# circuitdraft.net
KiCad netlist of a schematic drawn in EAGLE
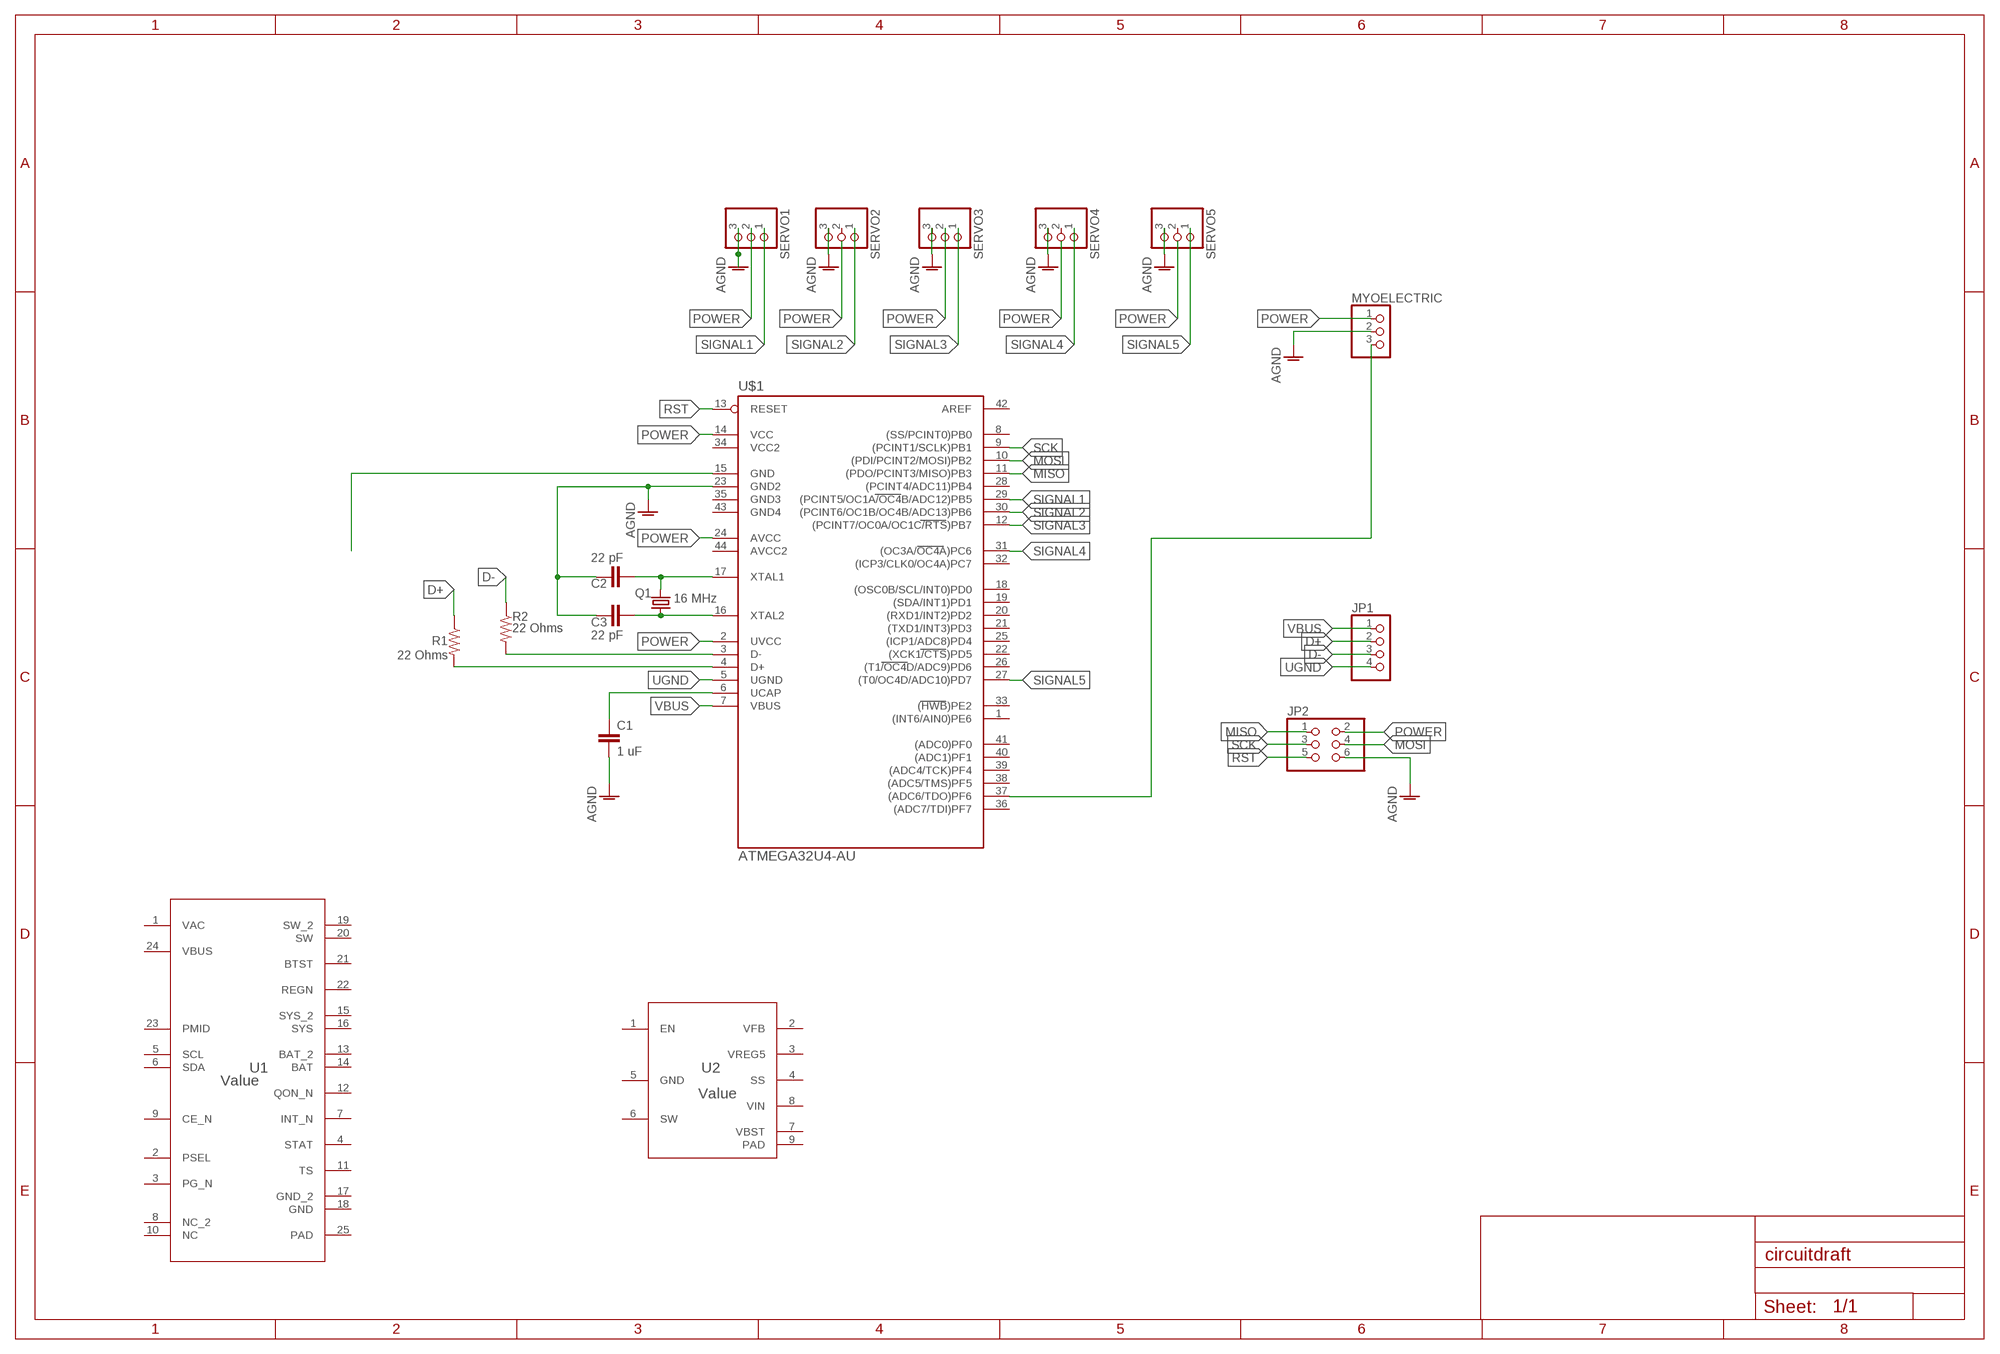
[diagram p0: schematic, sheet 1]

(export (version "E")
  (design (tool "Eeschema 10.0.6"))
  (components
    (comp (ref "C1")
      (value "1 uF")
      (footprint "eagle-import:C2.5-3")
      (libsource (lib "eagle-import") (part "C2,5-3"))
    )
    (comp (ref "C2")
      (value "22 pF")
      (footprint "eagle-import:C2.5-3")
      (libsource (lib "eagle-import") (part "C2,5-3"))
    )
    (comp (ref "C3")
      (value "22 pF")
      (footprint "eagle-import:C2.5-3")
      (libsource (lib "eagle-import") (part "C2,5-3"))
    )
    (comp (ref "JP1")
      (value "PINHD-1X4")
      (footprint "eagle-import:1X04")
      (libsource (lib "eagle-import") (part "PINHD-1X4"))
    )
    (comp (ref "JP2")
      (value "PINHD-2X3")
      (footprint "eagle-import:2X03")
      (libsource (lib "eagle-import") (part "PINHD-2X3"))
    )
    (comp (ref "MYOELECTRIC")
      (value "PINHD-1X3")
      (footprint "eagle-import:1X03")
      (libsource (lib "eagle-import") (part "PINHD-1X3"))
    )
    (comp (ref "Q1")
      (value "16 MHz")
      (footprint "eagle-import:HC49_S")
      (libsource (lib "eagle-import") (part "CRYSTALHC49S"))
    )
    (comp (ref "R1")
      (value "22 Ohms")
      (footprint "eagle-import:0204_7")
      (libsource (lib "eagle-import") (part "R-US_0204/7"))
    )
    (comp (ref "R2")
      (value "22 Ohms")
      (footprint "eagle-import:0204_7")
      (libsource (lib "eagle-import") (part "R-US_0204/7"))
    )
    (comp (ref "SERVO1")
      (value "PINHD-1X3")
      (footprint "eagle-import:1X03")
      (libsource (lib "eagle-import") (part "PINHD-1X3"))
    )
    (comp (ref "SERVO2")
      (value "PINHD-1X3")
      (footprint "eagle-import:1X03")
      (libsource (lib "eagle-import") (part "PINHD-1X3"))
    )
    (comp (ref "SERVO3")
      (value "PINHD-1X3")
      (footprint "eagle-import:1X03")
      (libsource (lib "eagle-import") (part "PINHD-1X3"))
    )
    (comp (ref "SERVO4")
      (value "PINHD-1X3")
      (footprint "eagle-import:1X03")
      (libsource (lib "eagle-import") (part "PINHD-1X3"))
    )
    (comp (ref "SERVO5")
      (value "PINHD-1X3")
      (footprint "eagle-import:1X03")
      (libsource (lib "eagle-import") (part "PINHD-1X3"))
    )
    (comp (ref "U$1")
      (value "ATMEGA32U4-AU")
      (footprint "eagle-import:TQFP44")
      (libsource (lib "eagle-import") (part "ATMEGA32U4-AU"))
    )
    (comp (ref "U1")
      (value "Value")
      (footprint "eagle-import:RTW0024H")
      (fields (field (name "MANUFACTURER") "Texas Instruments") (field (name "PARTNUMBER") "BQ25601RTWR"))
      (libsource (lib "eagle-import") (part "BQ25601RTWR"))
    )
    (comp (ref "U2")
      (value "Value")
      (footprint "eagle-import:DDA0008E_N")
      (fields
        (field (name "MANUFACTURER") "Texas Instruments")
        (field (name "PARTNUMBER") "UCC27211AQDDARQ1")
      )
      (libsource (lib "eagle-import") (part "UCC27211AQDDARQ1"))
    )
  )
  (nets
    (net (code "1") (name "/BAT") (class "Default")
      (node (ref "U1") (pin "14") (pinfunction "BAT_14") (pintype "power_in"))
    )
    (net (code "2") (name "/BAT_2") (class "Default")
      (node (ref "U1") (pin "13") (pinfunction "BAT_2_13") (pintype "power_in"))
    )
    (net (code "3") (name "/BTST") (class "Default")
      (node (ref "U1") (pin "21") (pinfunction "BTST_21") (pintype "power_in"))
    )
    (net (code "4") (name "/EN") (class "Default")
      (node (ref "U2") (pin "1") (pinfunction "EN_1") (pintype "power_in"))
    )
    (net (code "5") (name "/GND") (class "Default")
      (node (ref "U1") (pin "18") (pinfunction "GND_18") (pintype "power_in"))
    )
    (net (code "6") (name "/GND_2") (class "Default")
      (node (ref "U1") (pin "17") (pinfunction "GND_2_17") (pintype "power_in"))
    )
    (net (code "7") (name "/PAD") (class "Default")
      (node (ref "U1") (pin "25") (pinfunction "PAD_25") (pintype "power_in"))
    )
    (net (code "8") (name "/REGN") (class "Default")
      (node (ref "U1") (pin "22") (pinfunction "REGN_22") (pintype "power_in"))
    )
    (net (code "9") (name "/SS") (class "Default")
      (node (ref "U2") (pin "4") (pinfunction "SS_4") (pintype "power_in"))
    )
    (net (code "10") (name "/SW") (class "Default")
      (node (ref "U1") (pin "20") (pinfunction "SW_20") (pintype "power_in"))
    )
    (net (code "11") (name "/SW_2") (class "Default")
      (node (ref "U1") (pin "19") (pinfunction "SW_2_19") (pintype "power_in"))
    )
    (net (code "12") (name "/SYS") (class "Default")
      (node (ref "U1") (pin "16") (pinfunction "SYS_16") (pintype "power_in"))
    )
    (net (code "13") (name "/SYS_2") (class "Default")
      (node (ref "U1") (pin "15") (pinfunction "SYS_2_15") (pintype "power_in"))
    )
    (net (code "14") (name "/VAC") (class "Default")
      (node (ref "U1") (pin "1") (pinfunction "VAC_1") (pintype "power_in"))
    )
    (net (code "15") (name "/VBST") (class "Default")
      (node (ref "U2") (pin "7") (pinfunction "VBST_7") (pintype "power_in"))
    )
    (net (code "16") (name "/VFB") (class "Default")
      (node (ref "U2") (pin "2") (pinfunction "VFB_2") (pintype "power_in"))
    )
    (net (code "17") (name "AGND") (class "Default")
      (node (ref "C1") (pin "2") (pinfunction "2_2") (pintype "passive"))
      (node (ref "C2") (pin "1") (pinfunction "1_1") (pintype "passive"))
      (node (ref "C3") (pin "1") (pinfunction "1_1") (pintype "passive"))
      (node (ref "JP2") (pin "6") (pinfunction "6_6") (pintype "passive"))
      (node (ref "MYOELECTRIC") (pin "2") (pinfunction "2_2") (pintype "passive"))
      (node (ref "SERVO1") (pin "3") (pinfunction "3_3") (pintype "passive"))
      (node (ref "SERVO2") (pin "3") (pinfunction "3_3") (pintype "passive"))
      (node (ref "SERVO3") (pin "3") (pinfunction "3_3") (pintype "passive"))
      (node (ref "SERVO4") (pin "3") (pinfunction "3_3") (pintype "passive"))
      (node (ref "SERVO5") (pin "3") (pinfunction "3_3") (pintype "passive"))
      (node (ref "U$1") (pin "23") (pinfunction "GND2_23") (pintype "bidirectional"))
    )
    (net (code "18") (name "D+") (class "Default")
      (node (ref "JP1") (pin "2") (pinfunction "2_2") (pintype "passive"))
      (node (ref "R1") (pin "1") (pinfunction "1_1") (pintype "passive"))
    )
    (net (code "19") (name "D-") (class "Default")
      (node (ref "JP1") (pin "3") (pinfunction "3_3") (pintype "passive"))
      (node (ref "R2") (pin "1") (pinfunction "1_1") (pintype "passive"))
    )
    (net (code "20") (name "MISO") (class "Default")
      (node (ref "JP2") (pin "1") (pinfunction "1_1") (pintype "passive"))
      (node (ref "U$1") (pin "11") (pinfunction "(PDO/PCINT3/MISO)PB3_11") (pintype "bidirectional"))
    )
    (net (code "21") (name "MOSI") (class "Default")
      (node (ref "JP2") (pin "4") (pinfunction "4_4") (pintype "passive"))
      (node (ref "U$1") (pin "10") (pinfunction "(PDI/PCINT2/MOSI)PB2_10") (pintype "bidirectional"))
    )
    (net (code "22") (name "Net-(U$1-(ADC6{slash}TDO)PF6)") (class "Default")
      (node (ref "MYOELECTRIC") (pin "3") (pinfunction "3_3") (pintype "passive"))
      (node (ref "U$1") (pin "37") (pinfunction "(ADC6/TDO)PF6_37") (pintype "bidirectional"))
    )
    (net (code "23") (name "Net-(U$1-D+)") (class "Default")
      (node (ref "R1") (pin "2") (pinfunction "2_2") (pintype "passive"))
      (node (ref "U$1") (pin "4") (pinfunction "D+_4") (pintype "bidirectional"))
    )
    (net (code "24") (name "Net-(U$1-D-)") (class "Default")
      (node (ref "R2") (pin "2") (pinfunction "2_2") (pintype "passive"))
      (node (ref "U$1") (pin "3") (pinfunction "D-_3") (pintype "bidirectional"))
    )
    (net (code "25") (name "Net-(U$1-UCAP)") (class "Default")
      (node (ref "C1") (pin "1") (pinfunction "1_1") (pintype "passive"))
      (node (ref "U$1") (pin "6") (pinfunction "UCAP_6") (pintype "bidirectional"))
    )
    (net (code "26") (name "Net-(U$1-XTAL1)") (class "Default")
      (node (ref "C2") (pin "2") (pinfunction "2_2") (pintype "passive"))
      (node (ref "Q1") (pin "2") (pinfunction "2_2") (pintype "passive"))
      (node (ref "U$1") (pin "17") (pinfunction "XTAL1_17") (pintype "bidirectional"))
    )
    (net (code "27") (name "Net-(U$1-XTAL2)") (class "Default")
      (node (ref "C3") (pin "2") (pinfunction "2_2") (pintype "passive"))
      (node (ref "Q1") (pin "1") (pinfunction "1_1") (pintype "passive"))
      (node (ref "U$1") (pin "16") (pinfunction "XTAL2_16") (pintype "bidirectional"))
    )
    (net (code "28") (name "POWER") (class "Default")
      (node (ref "JP2") (pin "2") (pinfunction "2_2") (pintype "passive"))
      (node (ref "MYOELECTRIC") (pin "1") (pinfunction "1_1") (pintype "passive"))
      (node (ref "SERVO1") (pin "2") (pinfunction "2_2") (pintype "passive"))
      (node (ref "SERVO3") (pin "2") (pinfunction "2_2") (pintype "passive"))
      (node (ref "U$1") (pin "14") (pinfunction "VCC_14") (pintype "bidirectional"))
      (node (ref "U$1") (pin "2") (pinfunction "UVCC_2") (pintype "bidirectional"))
      (node (ref "U$1") (pin "24") (pinfunction "AVCC_24") (pintype "bidirectional"))
    )
    (net (code "29") (name "RST") (class "Default")
      (node (ref "JP2") (pin "5") (pinfunction "5_5") (pintype "passive"))
      (node (ref "U$1") (pin "13") (pinfunction "RESET_13") (pintype "bidirectional"))
    )
    (net (code "30") (name "SCK") (class "Default")
      (node (ref "JP2") (pin "3") (pinfunction "3_3") (pintype "passive"))
      (node (ref "U$1") (pin "9") (pinfunction "(PCINT1/SCLK)PB1_9") (pintype "bidirectional"))
    )
    (net (code "31") (name "SIGNAL1") (class "Default")
      (node (ref "SERVO1") (pin "1") (pinfunction "1_1") (pintype "passive"))
      (node (ref "U$1") (pin "29") (pinfunction "(PCINT5/OC1A/OC4B/ADC12)PB5_29") (pintype "bidirectional"))
    )
    (net (code "32") (name "SIGNAL2") (class "Default")
      (node (ref "SERVO2") (pin "1") (pinfunction "1_1") (pintype "passive"))
      (node (ref "U$1") (pin "30") (pinfunction "(PCINT6/OC1B/OC4B/ADC13)PB6_30") (pintype "bidirectional"))
    )
    (net (code "33") (name "SIGNAL3") (class "Default")
      (node (ref "SERVO3") (pin "1") (pinfunction "1_1") (pintype "passive"))
      (node (ref "U$1") (pin "12") (pinfunction "(PCINT7/OC0A/OC1C/RTS)PB7_12") (pintype "bidirectional"))
    )
    (net (code "34") (name "SIGNAL4") (class "Default")
      (node (ref "SERVO4") (pin "1") (pinfunction "1_1") (pintype "passive"))
      (node (ref "U$1") (pin "31") (pinfunction "(OC3A/OC4A)PC6_31") (pintype "bidirectional"))
    )
    (net (code "35") (name "SIGNAL5") (class "Default")
      (node (ref "SERVO5") (pin "1") (pinfunction "1_1") (pintype "passive"))
      (node (ref "U$1") (pin "27") (pinfunction "(T0/OC4D/ADC10)PD7_27") (pintype "bidirectional"))
    )
    (net (code "36") (name "UGND") (class "Default")
      (node (ref "JP1") (pin "4") (pinfunction "4_4") (pintype "passive"))
      (node (ref "U$1") (pin "5") (pinfunction "UGND_5") (pintype "bidirectional"))
    )
    (net (code "37") (name "VBUS") (class "Default")
      (node (ref "JP1") (pin "1") (pinfunction "1_1") (pintype "passive"))
      (node (ref "U$1") (pin "7") (pinfunction "VBUS_7") (pintype "bidirectional"))
    )
    (net (code "38") (name "unconnected-(SERVO2-Pad2)") (class "Default")
      (node (ref "SERVO2") (pin "2") (pinfunction "2_2") (pintype "passive"))
    )
    (net (code "39") (name "unconnected-(SERVO4-Pad2)") (class "Default")
      (node (ref "SERVO4") (pin "2") (pinfunction "2_2") (pintype "passive"))
    )
    (net (code "40") (name "unconnected-(SERVO5-Pad2)") (class "Default")
      (node (ref "SERVO5") (pin "2") (pinfunction "2_2") (pintype "passive"))
    )
    (net (code "41") (name "unconnected-(U$1-(ADC0)PF0-Pad41)") (class "Default")
      (node (ref "U$1") (pin "41") (pinfunction "(ADC0)PF0_41") (pintype "bidirectional"))
    )
    (net (code "42") (name "unconnected-(U$1-(ADC1)PF1-Pad40)") (class "Default")
      (node (ref "U$1") (pin "40") (pinfunction "(ADC1)PF1_40") (pintype "bidirectional"))
    )
    (net (code "43") (name "unconnected-(U$1-(ADC4{slash}TCK)PF4-Pad39)") (class "Default")
      (node (ref "U$1") (pin "39") (pinfunction "(ADC4/TCK)PF4_39") (pintype "bidirectional"))
    )
    (net (code "44") (name "unconnected-(U$1-(ADC5{slash}TMS)PF5-Pad38)") (class "Default")
      (node (ref "U$1") (pin "38") (pinfunction "(ADC5/TMS)PF5_38") (pintype "bidirectional"))
    )
    (net (code "45") (name "unconnected-(U$1-(ADC7{slash}TDI)PF7-Pad36)") (class "Default")
      (node (ref "U$1") (pin "36") (pinfunction "(ADC7/TDI)PF7_36") (pintype "bidirectional"))
    )
    (net (code "46") (name "unconnected-(U$1-(HWB)PE2-Pad33)") (class "Default")
      (node (ref "U$1") (pin "33") (pinfunction "(HWB)PE2_33") (pintype "bidirectional"))
    )
    (net (code "47") (name "unconnected-(U$1-(ICP1{slash}ADC8)PD4-Pad25)") (class "Default")
      (node (ref "U$1") (pin "25") (pinfunction "(ICP1/ADC8)PD4_25") (pintype "bidirectional"))
    )
    (net (code "48") (name "unconnected-(U$1-(ICP3{slash}CLK0{slash}OC4A)PC7-Pad32)") (class "Default")
      (node (ref "U$1") (pin "32") (pinfunction "(ICP3/CLK0/OC4A)PC7_32") (pintype "bidirectional"))
    )
    (net (code "49") (name "unconnected-(U$1-(INT6{slash}AIN0)PE6-Pad1)") (class "Default")
      (node (ref "U$1") (pin "1") (pinfunction "(INT6/AIN0)PE6_1") (pintype "bidirectional"))
    )
    (net (code "50") (name "unconnected-(U$1-(OSC0B{slash}SCL{slash}INT0)PD0-Pad18)") (class "Default")
      (node (ref "U$1") (pin "18") (pinfunction "(OSC0B/SCL/INT0)PD0_18") (pintype "bidirectional"))
    )
    (net (code "51") (name "unconnected-(U$1-(PCINT4{slash}ADC11)PB4-Pad28)") (class "Default")
      (node (ref "U$1") (pin "28") (pinfunction "(PCINT4/ADC11)PB4_28") (pintype "bidirectional"))
    )
    (net (code "52") (name "unconnected-(U$1-(RXD1{slash}INT2)PD2-Pad20)") (class "Default")
      (node (ref "U$1") (pin "20") (pinfunction "(RXD1/INT2)PD2_20") (pintype "bidirectional"))
    )
    (net (code "53") (name "unconnected-(U$1-(SDA{slash}INT1)PD1-Pad19)") (class "Default")
      (node (ref "U$1") (pin "19") (pinfunction "(SDA/INT1)PD1_19") (pintype "bidirectional"))
    )
    (net (code "54") (name "unconnected-(U$1-(SS{slash}PCINT0)PB0-Pad8)") (class "Default")
      (node (ref "U$1") (pin "8") (pinfunction "(SS/PCINT0)PB0_8") (pintype "bidirectional"))
    )
    (net (code "55") (name "unconnected-(U$1-(T1{slash}OC4D{slash}ADC9)PD6-Pad26)") (class "Default")
      (node (ref "U$1") (pin "26") (pinfunction "(T1/OC4D/ADC9)PD6_26") (pintype "bidirectional"))
    )
    (net (code "56") (name "unconnected-(U$1-(TXD1{slash}INT3)PD3-Pad21)") (class "Default")
      (node (ref "U$1") (pin "21") (pinfunction "(TXD1/INT3)PD3_21") (pintype "bidirectional"))
    )
    (net (code "57") (name "unconnected-(U$1-(XCK1{slash}CTS)PD5-Pad22)") (class "Default")
      (node (ref "U$1") (pin "22") (pinfunction "(XCK1/CTS)PD5_22") (pintype "bidirectional"))
    )
    (net (code "58") (name "unconnected-(U$1-AREF-Pad42)") (class "Default")
      (node (ref "U$1") (pin "42") (pinfunction "AREF_42") (pintype "bidirectional"))
    )
    (net (code "59") (name "unconnected-(U$1-AVCC2-Pad44)") (class "Default")
      (node (ref "U$1") (pin "44") (pinfunction "AVCC2_44") (pintype "bidirectional"))
    )
    (net (code "60") (name "unconnected-(U$1-GND-Pad15)") (class "Default")
      (node (ref "U$1") (pin "15") (pinfunction "GND_15") (pintype "bidirectional"))
    )
    (net (code "61") (name "unconnected-(U$1-GND3-Pad35)") (class "Default")
      (node (ref "U$1") (pin "35") (pinfunction "GND3_35") (pintype "bidirectional"))
    )
    (net (code "62") (name "unconnected-(U$1-GND4-Pad43)") (class "Default")
      (node (ref "U$1") (pin "43") (pinfunction "GND4_43") (pintype "bidirectional"))
    )
    (net (code "63") (name "unconnected-(U$1-VCC2-Pad34)") (class "Default")
      (node (ref "U$1") (pin "34") (pinfunction "VCC2_34") (pintype "bidirectional"))
    )
    (net (code "64") (name "unconnected-(U1-CE_N-Pad9)") (class "Default")
      (node (ref "U1") (pin "9") (pinfunction "CE_N_9") (pintype "input"))
    )
    (net (code "65") (name "unconnected-(U1-INT_N-Pad7)") (class "Default")
      (node (ref "U1") (pin "7") (pinfunction "INT_N_7") (pintype "open_collector"))
    )
    (net (code "66") (name "unconnected-(U1-NC-Pad10)") (class "Default")
      (node (ref "U1") (pin "10") (pinfunction "NC_10") (pintype "passive"))
    )
    (net (code "67") (name "unconnected-(U1-NC_2-Pad8)") (class "Default")
      (node (ref "U1") (pin "8") (pinfunction "NC_2_8") (pintype "passive"))
    )
    (net (code "68") (name "unconnected-(U1-PG_N-Pad3)") (class "Default")
      (node (ref "U1") (pin "3") (pinfunction "PG_N_3") (pintype "passive"))
    )
    (net (code "69") (name "unconnected-(U1-PMID-Pad23)") (class "Default")
      (node (ref "U1") (pin "23") (pinfunction "PMID_23") (pintype "output"))
    )
    (net (code "70") (name "unconnected-(U1-PSEL-Pad2)") (class "Default")
      (node (ref "U1") (pin "2") (pinfunction "PSEL_2") (pintype "passive"))
    )
    (net (code "71") (name "unconnected-(U1-QON_N-Pad12)") (class "Default")
      (node (ref "U1") (pin "12") (pinfunction "QON_N_12") (pintype "input"))
    )
    (net (code "72") (name "unconnected-(U1-SCL-Pad5)") (class "Default")
      (node (ref "U1") (pin "5") (pinfunction "SCL_5") (pintype "input"))
    )
    (net (code "73") (name "unconnected-(U1-SDA-Pad6)") (class "Default")
      (node (ref "U1") (pin "6") (pinfunction "SDA_6") (pintype "bidirectional"))
    )
    (net (code "74") (name "unconnected-(U1-STAT-Pad4)") (class "Default")
      (node (ref "U1") (pin "4") (pinfunction "STAT_4") (pintype "open_collector"))
    )
    (net (code "75") (name "unconnected-(U1-TS-Pad11)") (class "Default")
      (node (ref "U1") (pin "11") (pinfunction "TS_11") (pintype "input"))
    )
    (net (code "76") (name "unconnected-(U1-VBUS-Pad24)") (class "Default")
      (node (ref "U1") (pin "24") (pinfunction "VBUS_24") (pintype "passive"))
    )
    (net (code "77") (name "unconnected-(U2-GND-Pad5)") (class "Default")
      (node (ref "U2") (pin "5") (pinfunction "GND_5") (pintype "input"))
    )
    (net (code "78") (name "unconnected-(U2-PAD-Pad9)") (class "Default")
      (node (ref "U2") (pin "9") (pinfunction "PAD_9") (pintype "passive"))
    )
    (net (code "79") (name "unconnected-(U2-SW-Pad6)") (class "Default")
      (node (ref "U2") (pin "6") (pinfunction "SW_6") (pintype "input"))
    )
    (net (code "80") (name "unconnected-(U2-VIN-Pad8)") (class "Default")
      (node (ref "U2") (pin "8") (pinfunction "VIN_8") (pintype "output"))
    )
    (net (code "81") (name "unconnected-(U2-VREG5-Pad3)") (class "Default")
      (node (ref "U2") (pin "3") (pinfunction "VREG5_3") (pintype "output"))
    )
  )
)
